# CAN.net
KiCad netlist of a schematic drawn in Altium Designer
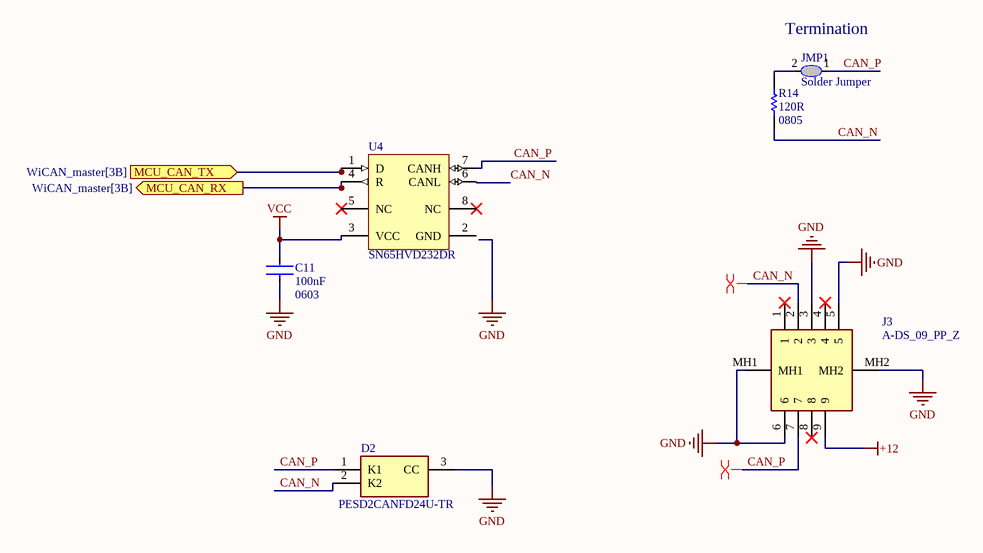
[diagram p0: CAN.SchDoc]

(export (version "E")
  (design (tool "Eeschema 10.0.6"))
  (components
    (comp (ref "C11")
      (value "CL10B104KB8WPNC")
      (footprint "FP-CL10-IPC_A")
      (description "Cap Ceramic 100nF 50V X7R ±10% Pad SMD 0603 +125°C T/R")
      (fields
        (field (name "CAPACITANCE") "100nF")
        (field (name "CASE/PACKAGE") "0603")
        (field (name "TOLERANCE") "10%")
      )
      (libsource (lib "Altium Content Vault") (part "b4654b650e69147ec39a6b967a45e02"))
    )
    (comp (ref "D2")
      (value "PESD2CANFD24U-TR")
      (footprint "SOT95P230X110-3N")
      (description "Diode")
      (fields (field (name "MOUSER PART NUMBER") "771-PESD2CANFD24U-TR"))
      (libsource (lib "WiCAN_lib") (part "PESD2CANFD24U-TR"))
    )
    (comp (ref "J3")
      (value "A-DS_09_PP_Z")
      (footprint "ADS09PPZ")
      (description "Connector")
      (fields (field (name "MANUFACTURER_PART_NUMBER") "A-DS 09 PP/Z"))
      (libsource (lib "WiCAN_lib") (part "A-DS_09_PP_Z"))
    )
    (comp (ref "JMP1")
      (value "Solder Jumper")
      (footprint "Solder Jumper")
      (libsource (lib "WiCAN_lib") (part "Solder Jumper"))
    )
    (comp (ref "R14")
      (value "ERJ-P06J121V")
      (footprint "RESC2013X70X40LL20T20")
      (fields
        (field (name "MANUFACTURER") "Panasonic")
        (field (name "RESISTANCE") "120R")
        (field (name "PACKAGE") "0805")
      )
      (libsource (lib "Altium Content Vault") (part "RES"))
    )
    (comp (ref "U4")
      (value "SN65HVD232DR")
      (footprint "D0008A_M")
      (description "3.3 V Can Transceiver, 17 mA, -40 to 85 degC, 8-pin SOIC (D), Green (RoHS & no Sb/Br)")
      (fields (field (name "MANUFACTURER") "Texas Instruments"))
      (libsource (lib "Altium Content Vault") (part "TI-SN65HVD232-SOIC_D-8"))
    )
  )
  (nets
    (net (code "1") (name "+12") (class "Default")
      (node (ref "J3") (pin "9") (pinfunction "9_9") (pintype "passive"))
    )
    (net (code "2") (name "/CAN_N") (class "Default")
      (node (ref "D2") (pin "2") (pinfunction "K2_2") (pintype "passive"))
      (node (ref "J3") (pin "2") (pinfunction "2_2") (pintype "passive"))
      (node (ref "R14") (pin "2") (pinfunction "2_2") (pintype "passive"))
      (node (ref "U4") (pin "6") (pinfunction "CANL_6") (pintype "bidirectional"))
    )
    (net (code "3") (name "/CAN_P") (class "Default")
      (node (ref "D2") (pin "1") (pinfunction "K1_1") (pintype "passive"))
      (node (ref "J3") (pin "7") (pinfunction "7_7") (pintype "passive"))
      (node (ref "JMP1") (pin "1") (pinfunction "1_1") (pintype "passive"))
      (node (ref "U4") (pin "7") (pinfunction "CANH_7") (pintype "bidirectional"))
    )
    (net (code "4") (name "/MCU_CAN_RX") (class "Default")
      (node (ref "U4") (pin "4") (pinfunction "R_4") (pintype "output"))
    )
    (net (code "5") (name "/MCU_CAN_TX") (class "Default")
      (node (ref "U4") (pin "1") (pinfunction "D_1") (pintype "input"))
    )
    (net (code "6") (name "GND") (class "Default")
      (node (ref "C11") (pin "1") (pinfunction "1_1") (pintype "passive"))
      (node (ref "D2") (pin "3") (pinfunction "CC_3") (pintype "passive"))
      (node (ref "J3") (pin "3") (pinfunction "3_3") (pintype "passive"))
      (node (ref "J3") (pin "5") (pinfunction "5_5") (pintype "passive"))
      (node (ref "J3") (pin "6") (pinfunction "6_6") (pintype "passive"))
      (node (ref "J3") (pin "MH1") (pinfunction "MH1_MH1") (pintype "passive"))
      (node (ref "J3") (pin "MH2") (pinfunction "MH2_MH2") (pintype "passive"))
    )
    (net (code "7") (name "Net-(JMP1-Pad2)") (class "Default")
      (node (ref "JMP1") (pin "2") (pinfunction "2_2") (pintype "passive"))
      (node (ref "R14") (pin "1") (pinfunction "1_1") (pintype "passive"))
    )
    (net (code "8") (name "VCC") (class "Default")
      (node (ref "C11") (pin "2") (pinfunction "2_2") (pintype "passive"))
      (node (ref "U4") (pin "3") (pinfunction "VCC_3") (pintype "power_in"))
    )
    (net (code "9") (name "unconnected-(J3-Pad1)") (class "Default")
      (node (ref "J3") (pin "1") (pinfunction "1_1") (pintype "passive+no_connect"))
    )
    (net (code "10") (name "unconnected-(J3-Pad4)") (class "Default")
      (node (ref "J3") (pin "4") (pinfunction "4_4") (pintype "passive+no_connect"))
    )
    (net (code "11") (name "unconnected-(J3-Pad8)") (class "Default")
      (node (ref "J3") (pin "8") (pinfunction "8_8") (pintype "passive+no_connect"))
    )
    (net (code "12") (name "unconnected-(U4-GND-Pad2)") (class "Default")
      (node (ref "U4") (pin "2") (pinfunction "GND_2") (pintype "power_in"))
    )
    (net (code "13") (name "unconnected-(U4-NC-Pad5)") (class "Default")
      (node (ref "U4") (pin "5") (pinfunction "NC_5") (pintype "passive+no_connect"))
    )
    (net (code "14") (name "unconnected-(U4-NC-Pad8)") (class "Default")
      (node (ref "U4") (pin "8") (pinfunction "NC_8") (pintype "passive+no_connect"))
    )
  )
)
